# STlink-plug.net
KiCad netlist of a schematic drawn in Altium Designer
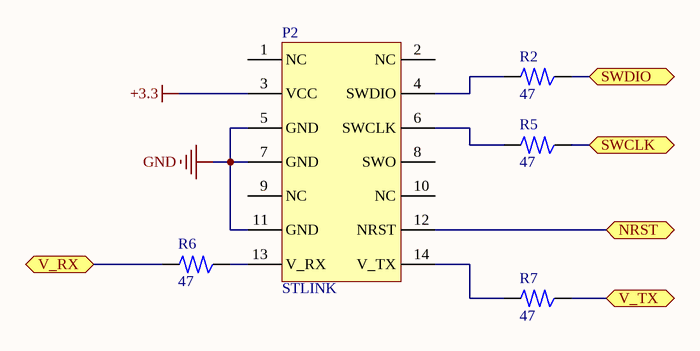
[diagram p0: STlink-plug.SchDoc]

(export (version "E")
  (design (tool "Eeschema 10.0.6"))
  (components
    (comp (ref "P2")
      (value "STLINK")
      (footprint "SMT_CON_SAMTEC_FTSH-107-01-L-DV-K")
      (description "Connector 14-pin Samtec FTSH-107-01-L-DV-K 1.27mm Pitch SMT")
      (libsource (lib "SMT_CON_SAMTEC_FTSH-107-01-L-DV-K") (part "SMT_CON_SAMTEC_FTSH-107-01-L-DV-K"))
    )
    (comp (ref "R2")
      (value "47")
      (footprint "SMT_RES_0805(2012)")
      (description "0805(2012) Resistor 1/4-1/8W 150V 2A")
      (libsource (lib "SMT_RES_0805(2012)") (part "SMT_RES_0805(2012)"))
    )
    (comp (ref "R5")
      (value "47")
      (footprint "SMT_RES_0805(2012)")
      (description "0805(2012) Resistor 1/4-1/8W 150V 2A")
      (libsource (lib "SMT_RES_0805(2012)") (part "SMT_RES_0805(2012)"))
    )
    (comp (ref "R6")
      (value "47")
      (footprint "SMT_RES_0805(2012)")
      (description "0805(2012) Resistor 1/4-1/8W 150V 2A")
      (libsource (lib "SMT_RES_0805(2012)") (part "SMT_RES_0805(2012)"))
    )
    (comp (ref "R7")
      (value "47")
      (footprint "SMT_RES_0805(2012)")
      (description "0805(2012) Resistor 1/4-1/8W 150V 2A")
      (libsource (lib "SMT_RES_0805(2012)") (part "SMT_RES_0805(2012)"))
    )
  )
  (nets
    (net (code "1") (name "+3.3") (class "Default")
      (node (ref "P2") (pin "3") (pinfunction "VCC_3") (pintype "passive"))
    )
    (net (code "2") (name "/NRST") (class "Default")
      (node (ref "P2") (pin "12") (pinfunction "NRST_12") (pintype "passive"))
    )
    (net (code "3") (name "/SWCLK") (class "Default")
      (node (ref "R5") (pin "2") (pinfunction "2_2") (pintype "passive"))
    )
    (net (code "4") (name "/SWDIO") (class "Default")
      (node (ref "R2") (pin "2") (pinfunction "2_2") (pintype "passive"))
    )
    (net (code "5") (name "/V_RX") (class "Default")
      (node (ref "R6") (pin "1") (pinfunction "1_1") (pintype "passive"))
    )
    (net (code "6") (name "/V_TX") (class "Default")
      (node (ref "R7") (pin "2") (pinfunction "2_2") (pintype "passive"))
    )
    (net (code "7") (name "GND") (class "Default")
      (node (ref "P2") (pin "11") (pinfunction "GND_11") (pintype "passive"))
      (node (ref "P2") (pin "5") (pinfunction "GND_5") (pintype "passive"))
      (node (ref "P2") (pin "7") (pinfunction "GND_7") (pintype "passive"))
    )
    (net (code "8") (name "Net-(P2-SWCLK)") (class "Default")
      (node (ref "P2") (pin "6") (pinfunction "SWCLK_6") (pintype "passive"))
      (node (ref "R5") (pin "1") (pinfunction "1_1") (pintype "passive"))
    )
    (net (code "9") (name "Net-(P2-SWDIO)") (class "Default")
      (node (ref "P2") (pin "4") (pinfunction "SWDIO_4") (pintype "passive"))
      (node (ref "R2") (pin "1") (pinfunction "1_1") (pintype "passive"))
    )
    (net (code "10") (name "Net-(P2-V_RX)") (class "Default")
      (node (ref "P2") (pin "13") (pinfunction "V_RX_13") (pintype "passive"))
      (node (ref "R6") (pin "2") (pinfunction "2_2") (pintype "passive"))
    )
    (net (code "11") (name "Net-(P2-V_TX)") (class "Default")
      (node (ref "P2") (pin "14") (pinfunction "V_TX_14") (pintype "passive"))
      (node (ref "R7") (pin "1") (pinfunction "1_1") (pintype "passive"))
    )
    (net (code "12") (name "unconnected-(P2-NC-Pad1)") (class "Default")
      (node (ref "P2") (pin "1") (pinfunction "NC_1") (pintype "passive"))
    )
    (net (code "13") (name "unconnected-(P2-NC-Pad2)") (class "Default")
      (node (ref "P2") (pin "2") (pinfunction "NC_2") (pintype "passive"))
    )
    (net (code "14") (name "unconnected-(P2-NC-Pad9)") (class "Default")
      (node (ref "P2") (pin "9") (pinfunction "NC_9") (pintype "passive"))
    )
    (net (code "15") (name "unconnected-(P2-NC-Pad10)") (class "Default")
      (node (ref "P2") (pin "10") (pinfunction "NC_10") (pintype "passive"))
    )
    (net (code "16") (name "unconnected-(P2-SWO-Pad8)") (class "Default")
      (node (ref "P2") (pin "8") (pinfunction "SWO_8") (pintype "passive"))
    )
  )
)
